# ds1307.net
KiCad netlist of a schematic drawn in EAGLE
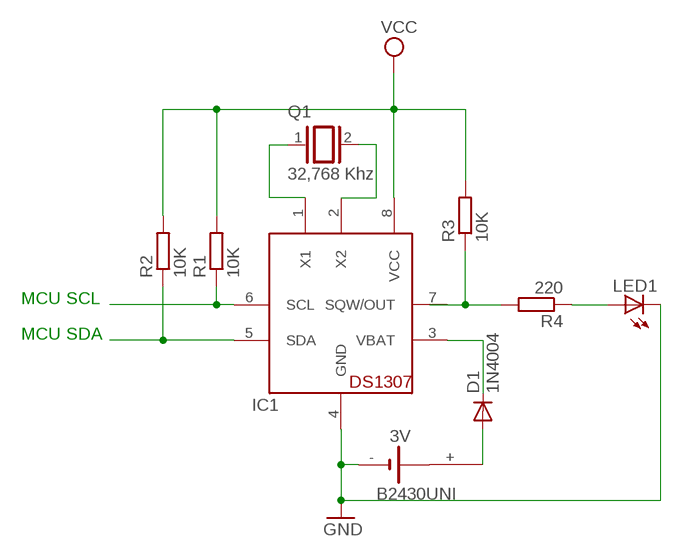
[diagram p0: schematic, sheet 1]

(export (version "E")
  (design (tool "Eeschema 10.0.6"))
  (components
    (comp (ref "3V")
      (value "B2430UNI")
      (footprint "eagle-import:B2430UNI")
      (libsource (lib "eagle-import") (part "B2430UNI"))
    )
    (comp (ref "D1")
      (value "1N4004")
      (footprint "eagle-import:DO41-10")
      (libsource (lib "eagle-import") (part "1N4004"))
    )
    (comp (ref "IC1")
      (value "DS1307")
      (footprint "eagle-import:DIL08")
      (libsource (lib "eagle-import") (part "DS1307"))
    )
    (comp (ref "LED1")
      (value "LED5MM")
      (footprint "eagle-import:LED5MM")
      (libsource (lib "eagle-import") (part "LED5MM"))
    )
    (comp (ref "Q1")
      (value "32,768 Khz")
      (footprint "eagle-import:Q")
      (libsource (lib "eagle-import") (part "XTAL"))
    )
    (comp (ref "R1")
      (value "10K")
      (footprint "eagle-import:0204_7")
      (libsource (lib "eagle-import") (part "R-EU_0204/7"))
    )
    (comp (ref "R2")
      (value "10K")
      (footprint "eagle-import:0204_7")
      (libsource (lib "eagle-import") (part "R-EU_0204/7"))
    )
    (comp (ref "R3")
      (value "10K")
      (footprint "eagle-import:0204_7")
      (libsource (lib "eagle-import") (part "R-EU_0204/7"))
    )
    (comp (ref "R4")
      (value "220")
      (footprint "eagle-import:0204_7")
      (libsource (lib "eagle-import") (part "R-EU_0204/7"))
    )
  )
  (nets
    (net (code "1") (name "GND") (class "Default")
      (node (ref "3V") (pin "-") (pinfunction "-_-") (pintype "passive"))
      (node (ref "IC1") (pin "4") (pinfunction "GND_4") (pintype "power_in"))
      (node (ref "LED1") (pin "K") (pinfunction "C_K") (pintype "passive"))
    )
    (net (code "2") (name "Net-(3V-Pad+)") (class "Default")
      (node (ref "3V") (pin "+") (pinfunction "+_+") (pintype "passive"))
      (node (ref "D1") (pin "A") (pinfunction "A_A") (pintype "passive"))
    )
    (net (code "3") (name "Net-(IC1-SCL)") (class "Default")
      (node (ref "IC1") (pin "6") (pinfunction "SCL_6") (pintype "bidirectional"))
      (node (ref "R1") (pin "1") (pinfunction "1_1") (pintype "passive"))
    )
    (net (code "4") (name "Net-(IC1-SDA)") (class "Default")
      (node (ref "IC1") (pin "5") (pinfunction "SDA_5") (pintype "bidirectional"))
      (node (ref "R2") (pin "1") (pinfunction "1_1") (pintype "passive"))
    )
    (net (code "5") (name "Net-(IC1-VBAT)") (class "Default")
      (node (ref "D1") (pin "C") (pinfunction "C_C") (pintype "passive"))
      (node (ref "IC1") (pin "3") (pinfunction "VBAT_3") (pintype "power_in"))
    )
    (net (code "6") (name "Net-(IC1-X1)") (class "Default")
      (node (ref "IC1") (pin "1") (pinfunction "X1_1") (pintype "passive"))
      (node (ref "Q1") (pin "1") (pinfunction "1_1") (pintype "passive"))
    )
    (net (code "7") (name "Net-(IC1-X2)") (class "Default")
      (node (ref "IC1") (pin "2") (pinfunction "X2_2") (pintype "passive"))
      (node (ref "Q1") (pin "2") (pinfunction "2_2") (pintype "passive"))
    )
    (net (code "8") (name "Net-(LED1-PadA)") (class "Default")
      (node (ref "LED1") (pin "A") (pinfunction "A_A") (pintype "passive"))
      (node (ref "R4") (pin "1") (pinfunction "1_1") (pintype "passive"))
    )
    (net (code "9") (name "Net-(R3-Pad1)") (class "Default")
      (node (ref "R3") (pin "1") (pinfunction "1_1") (pintype "passive"))
      (node (ref "R4") (pin "2") (pinfunction "2_2") (pintype "passive"))
    )
    (net (code "10") (name "VCC") (class "Default")
      (node (ref "IC1") (pin "8") (pinfunction "VCC_8") (pintype "power_in"))
      (node (ref "R1") (pin "2") (pinfunction "2_2") (pintype "passive"))
      (node (ref "R2") (pin "2") (pinfunction "2_2") (pintype "passive"))
      (node (ref "R3") (pin "2") (pinfunction "2_2") (pintype "passive"))
    )
    (net (code "11") (name "unconnected-(3V-+-Pad+@1)") (class "Default")
      (node (ref "3V") (pin "+@1") (pinfunction "+_+@1") (pintype "passive"))
    )
    (net (code "12") (name "unconnected-(3V-+-Pad+@2)") (class "Default")
      (node (ref "3V") (pin "+@2") (pinfunction "+_+@2") (pintype "passive"))
    )
    (net (code "13") (name "unconnected-(3V-+-Pad+@3)") (class "Default")
      (node (ref "3V") (pin "+@3") (pinfunction "+_+@3") (pintype "passive"))
    )
    (net (code "14") (name "unconnected-(3V-+-Pad+@4)") (class "Default")
      (node (ref "3V") (pin "+@4") (pinfunction "+_+@4") (pintype "passive"))
    )
    (net (code "15") (name "unconnected-(3V---Pad-@1)") (class "Default")
      (node (ref "3V") (pin "-@1") (pinfunction "-_-@1") (pintype "passive"))
    )
    (net (code "16") (name "unconnected-(IC1-SQW{slash}OUT-Pad7)") (class "Default")
      (node (ref "IC1") (pin "7") (pinfunction "SQW/OUT_7") (pintype "bidirectional"))
    )
  )
)
